# dac_board.net
KiCad netlist of a schematic drawn in EAGLE
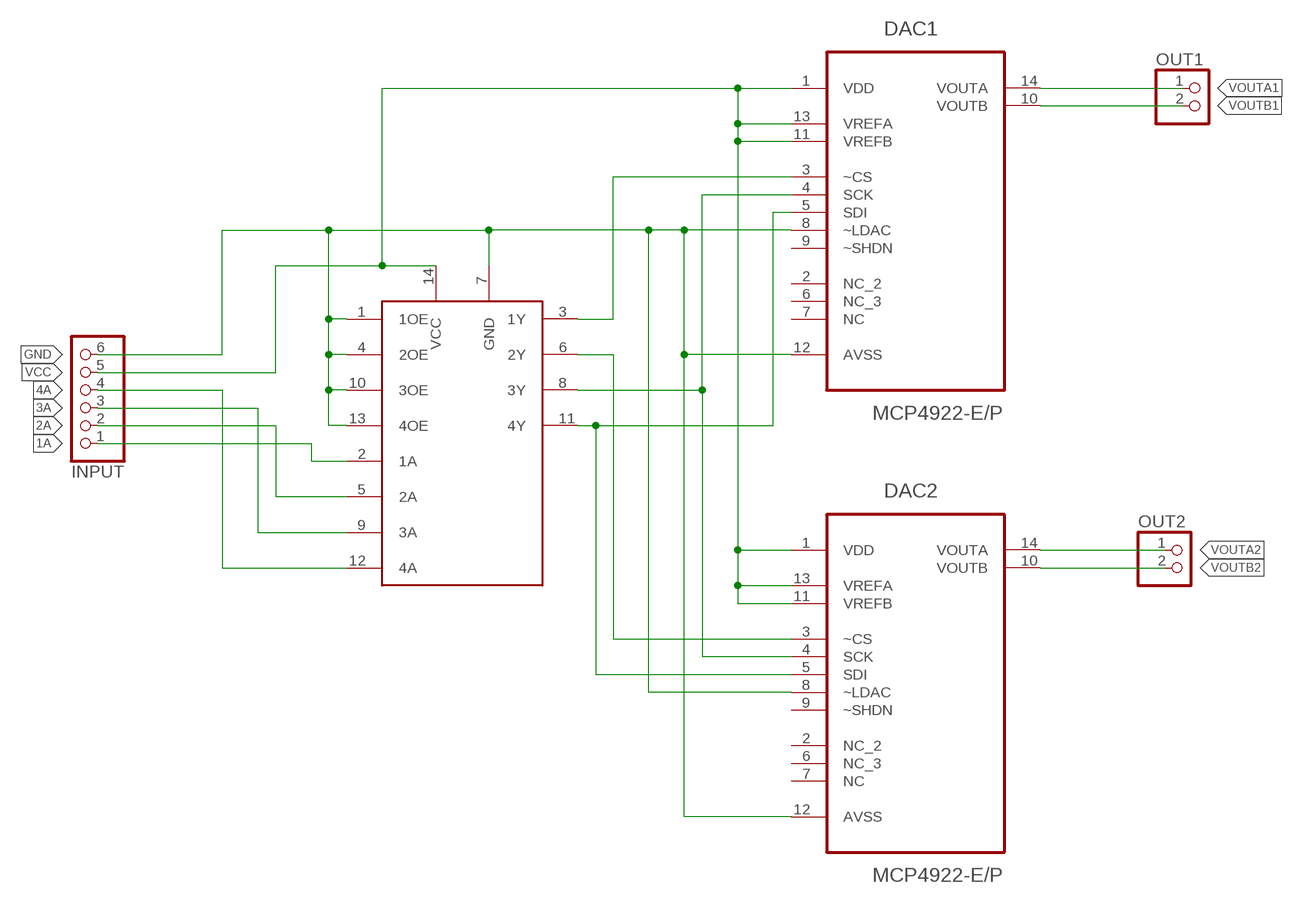
[diagram p0: schematic, sheet 1]

(export (version "E")
  (design (tool "Eeschema 10.0.6"))
  (components
    (comp (ref "DAC1")
      (value "MCP4922-E/P")
      (footprint "eagle-import:DIP254P762X533-14")
      (fields (field (name "MF") "Microchip"))
      (libsource (lib "eagle-import") (part "MCP4922-E/P"))
    )
    (comp (ref "DAC2")
      (value "MCP4922-E/P")
      (footprint "eagle-import:DIP254P762X533-14")
      (fields (field (name "MF") "Microchip"))
      (libsource (lib "eagle-import") (part "MCP4922-E/P"))
    )
    (comp (ref "INPUT")
      (value "PINHD-1X6")
      (footprint "eagle-import:1X06")
      (libsource (lib "eagle-import") (part "PINHD-1X6"))
    )
    (comp (ref "LLS")
      (value "SN74AHCT125")
      (footprint "eagle-import:DIP762W46P254L1930H508Q14")
      (libsource (lib "eagle-import") (part "SN74AHCT125"))
    )
    (comp (ref "OUT1")
      (value "PINHD-1X2")
      (footprint "eagle-import:1X02")
      (libsource (lib "eagle-import") (part "PINHD-1X2"))
    )
    (comp (ref "OUT2")
      (value "PINHD-1X2")
      (footprint "eagle-import:1X02")
      (libsource (lib "eagle-import") (part "PINHD-1X2"))
    )
  )
  (nets
    (net (code "1") (name "1A") (class "Default")
      (node (ref "INPUT") (pin "1") (pinfunction "1_1") (pintype "passive"))
      (node (ref "LLS") (pin "2") (pinfunction "1A_2") (pintype "bidirectional"))
    )
    (net (code "2") (name "2A") (class "Default")
      (node (ref "INPUT") (pin "2") (pinfunction "2_2") (pintype "passive"))
      (node (ref "LLS") (pin "5") (pinfunction "2A_5") (pintype "bidirectional"))
    )
    (net (code "3") (name "3A") (class "Default")
      (node (ref "INPUT") (pin "3") (pinfunction "3_3") (pintype "passive"))
      (node (ref "LLS") (pin "9") (pinfunction "3A_9") (pintype "bidirectional"))
    )
    (net (code "4") (name "4A") (class "Default")
      (node (ref "INPUT") (pin "4") (pinfunction "4_4") (pintype "passive"))
      (node (ref "LLS") (pin "12") (pinfunction "4A_12") (pintype "bidirectional"))
    )
    (net (code "5") (name "GND") (class "Default")
      (node (ref "DAC1") (pin "12") (pinfunction "AVSS_12") (pintype "power_in"))
      (node (ref "DAC1") (pin "8") (pinfunction "~{LDAC}_8") (pintype "input"))
      (node (ref "DAC2") (pin "12") (pinfunction "AVSS_12") (pintype "power_in"))
      (node (ref "DAC2") (pin "8") (pinfunction "~{LDAC}_8") (pintype "input"))
      (node (ref "INPUT") (pin "6") (pinfunction "6_6") (pintype "passive"))
      (node (ref "LLS") (pin "1") (pinfunction "1OE_1") (pintype "bidirectional"))
      (node (ref "LLS") (pin "10") (pinfunction "3OE_10") (pintype "bidirectional"))
      (node (ref "LLS") (pin "13") (pinfunction "4OE_13") (pintype "bidirectional"))
      (node (ref "LLS") (pin "4") (pinfunction "2OE_4") (pintype "bidirectional"))
      (node (ref "LLS") (pin "7") (pinfunction "GND_7") (pintype "bidirectional"))
    )
    (net (code "6") (name "Net-(DAC1-SCK)") (class "Default")
      (node (ref "DAC1") (pin "4") (pinfunction "SCK_4") (pintype "input"))
      (node (ref "DAC2") (pin "4") (pinfunction "SCK_4") (pintype "input"))
      (node (ref "LLS") (pin "8") (pinfunction "3Y_8") (pintype "bidirectional"))
    )
    (net (code "7") (name "Net-(DAC1-SDI)") (class "Default")
      (node (ref "DAC1") (pin "5") (pinfunction "SDI_5") (pintype "input"))
      (node (ref "DAC2") (pin "5") (pinfunction "SDI_5") (pintype "input"))
      (node (ref "LLS") (pin "11") (pinfunction "4Y_11") (pintype "bidirectional"))
    )
    (net (code "8") (name "Net-(DAC1-~{CS})") (class "Default")
      (node (ref "DAC1") (pin "3") (pinfunction "~{CS}_3") (pintype "input"))
      (node (ref "LLS") (pin "3") (pinfunction "1Y_3") (pintype "bidirectional"))
    )
    (net (code "9") (name "Net-(DAC2-~{CS})") (class "Default")
      (node (ref "DAC2") (pin "3") (pinfunction "~{CS}_3") (pintype "input"))
      (node (ref "LLS") (pin "6") (pinfunction "2Y_6") (pintype "bidirectional"))
    )
    (net (code "10") (name "VCC") (class "Default")
      (node (ref "DAC1") (pin "1") (pinfunction "VDD_1") (pintype "power_in"))
      (node (ref "DAC1") (pin "11") (pinfunction "VREFB_11") (pintype "input"))
      (node (ref "DAC1") (pin "13") (pinfunction "VREFA_13") (pintype "input"))
      (node (ref "DAC2") (pin "1") (pinfunction "VDD_1") (pintype "power_in"))
      (node (ref "DAC2") (pin "11") (pinfunction "VREFB_11") (pintype "input"))
      (node (ref "DAC2") (pin "13") (pinfunction "VREFA_13") (pintype "input"))
      (node (ref "INPUT") (pin "5") (pinfunction "5_5") (pintype "passive"))
      (node (ref "LLS") (pin "14") (pinfunction "VCC_14") (pintype "bidirectional"))
    )
    (net (code "11") (name "VOUTA1") (class "Default")
      (node (ref "DAC1") (pin "14") (pinfunction "VOUTA_14") (pintype "output"))
      (node (ref "OUT1") (pin "1") (pinfunction "1_1") (pintype "passive"))
    )
    (net (code "12") (name "VOUTA2") (class "Default")
      (node (ref "DAC2") (pin "14") (pinfunction "VOUTA_14") (pintype "output"))
      (node (ref "OUT2") (pin "1") (pinfunction "1_1") (pintype "passive"))
    )
    (net (code "13") (name "VOUTB1") (class "Default")
      (node (ref "DAC1") (pin "10") (pinfunction "VOUTB_10") (pintype "output"))
      (node (ref "OUT1") (pin "2") (pinfunction "2_2") (pintype "passive"))
    )
    (net (code "14") (name "VOUTB2") (class "Default")
      (node (ref "DAC2") (pin "10") (pinfunction "VOUTB_10") (pintype "output"))
      (node (ref "OUT2") (pin "2") (pinfunction "2_2") (pintype "passive"))
    )
    (net (code "15") (name "unconnected-(DAC1-NC-Pad7)") (class "Default")
      (node (ref "DAC1") (pin "7") (pinfunction "NC_7") (pintype "no_connect"))
    )
    (net (code "16") (name "unconnected-(DAC1-NC_2-Pad2)") (class "Default")
      (node (ref "DAC1") (pin "2") (pinfunction "NC_2_2") (pintype "no_connect"))
    )
    (net (code "17") (name "unconnected-(DAC1-NC_3-Pad6)") (class "Default")
      (node (ref "DAC1") (pin "6") (pinfunction "NC_3_6") (pintype "no_connect"))
    )
    (net (code "18") (name "unconnected-(DAC1-~{SHDN}-Pad9)") (class "Default")
      (node (ref "DAC1") (pin "9") (pinfunction "~{SHDN}_9") (pintype "input"))
    )
    (net (code "19") (name "unconnected-(DAC2-NC-Pad7)") (class "Default")
      (node (ref "DAC2") (pin "7") (pinfunction "NC_7") (pintype "no_connect"))
    )
    (net (code "20") (name "unconnected-(DAC2-NC_2-Pad2)") (class "Default")
      (node (ref "DAC2") (pin "2") (pinfunction "NC_2_2") (pintype "no_connect"))
    )
    (net (code "21") (name "unconnected-(DAC2-NC_3-Pad6)") (class "Default")
      (node (ref "DAC2") (pin "6") (pinfunction "NC_3_6") (pintype "no_connect"))
    )
    (net (code "22") (name "unconnected-(DAC2-~{SHDN}-Pad9)") (class "Default")
      (node (ref "DAC2") (pin "9") (pinfunction "~{SHDN}_9") (pintype "input"))
    )
  )
)
